# Adafruit-FONA-800-GSM-Breakout.net
KiCad netlist of a schematic drawn in EAGLE
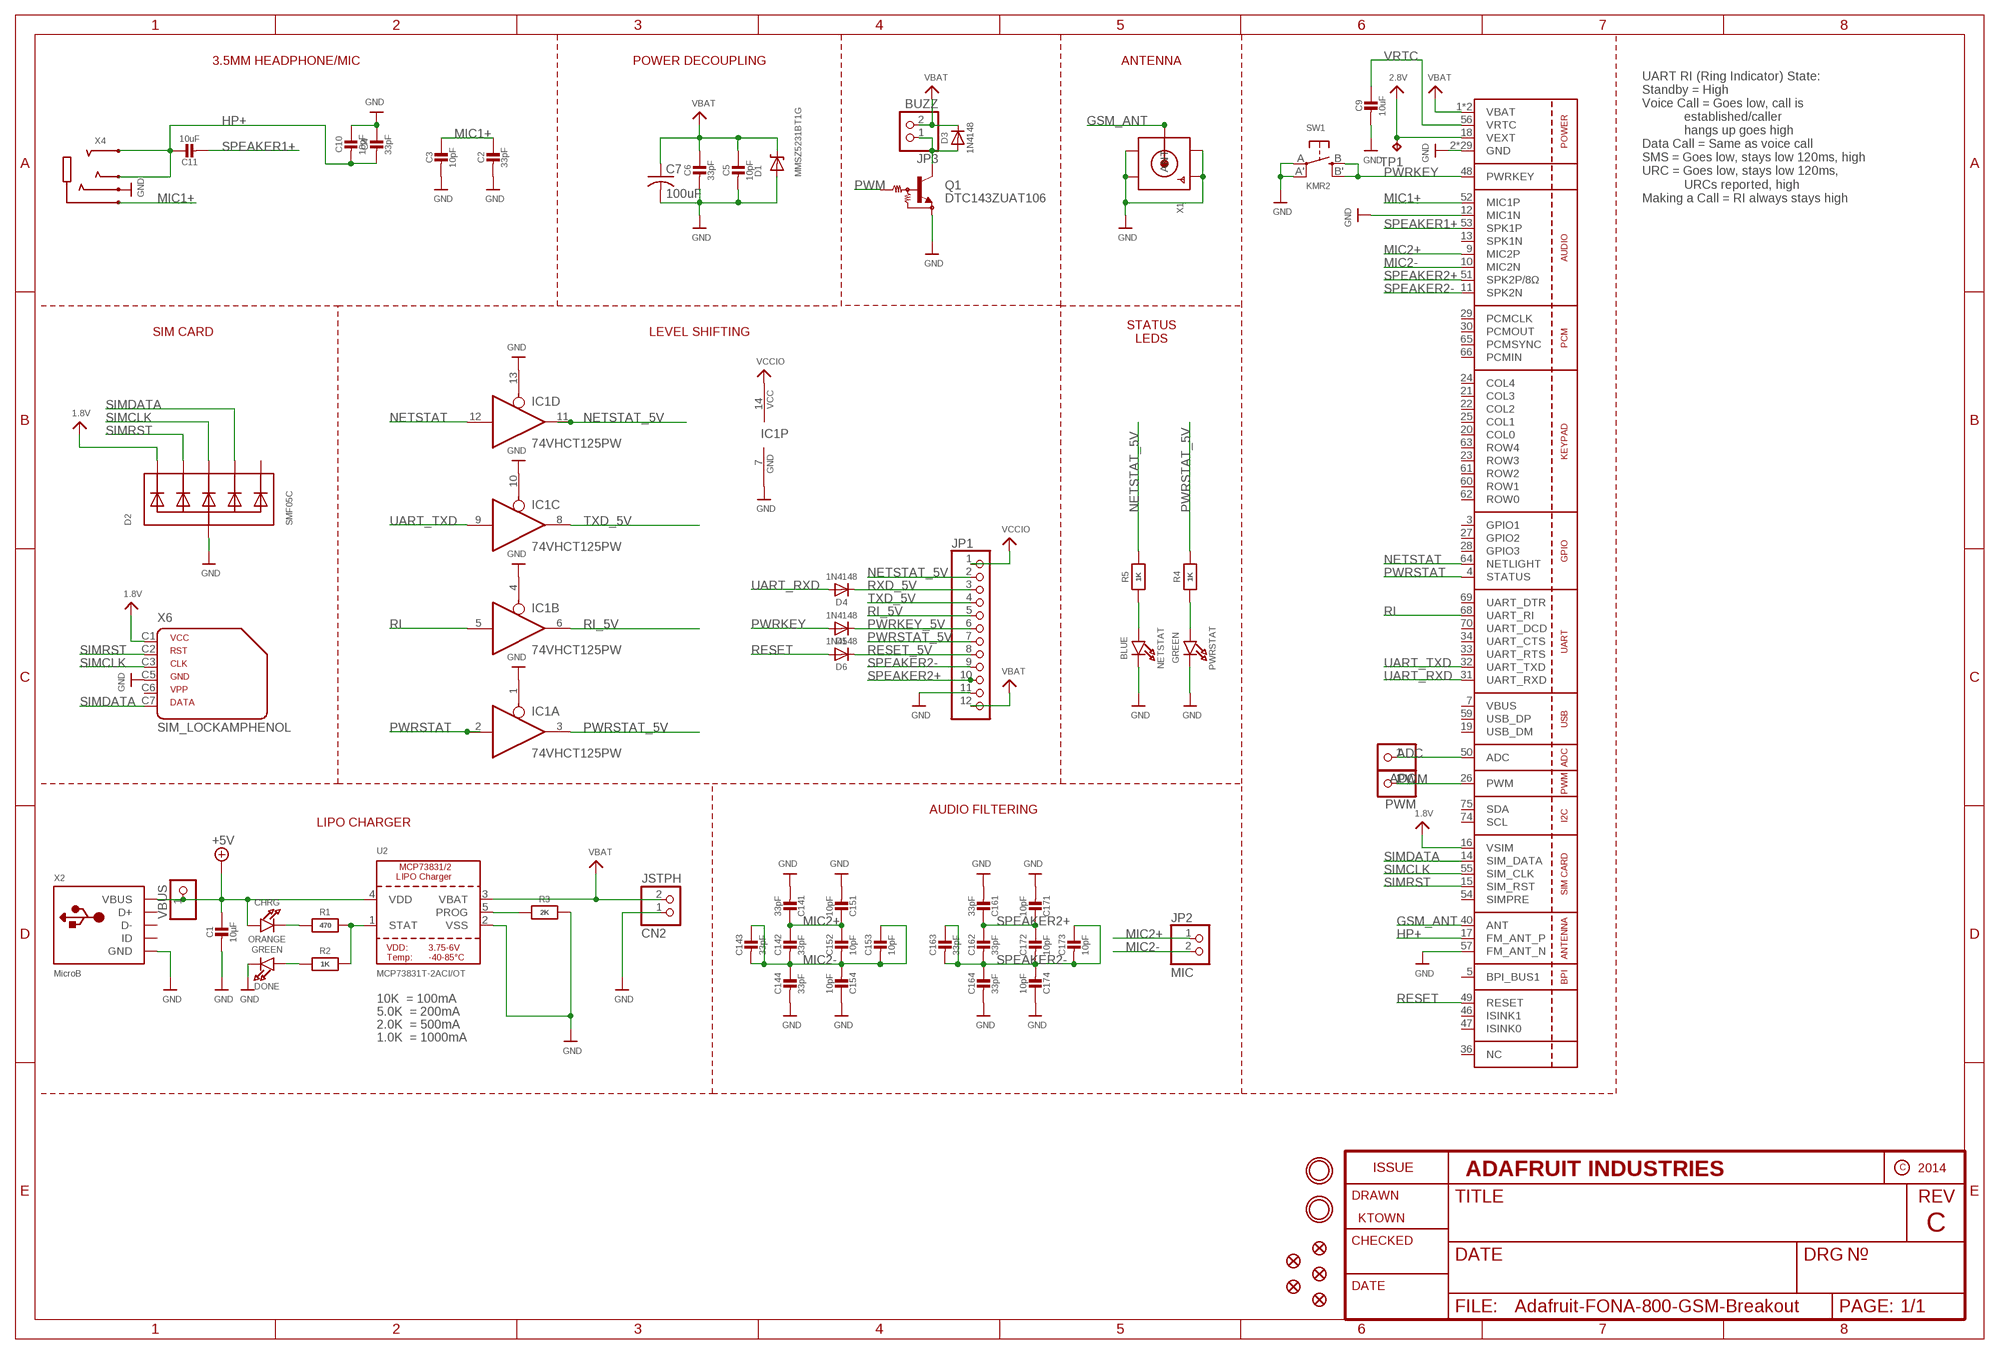
[diagram p0: schematic, sheet 1]

(export (version "E")
  (design (tool "Eeschema 10.0.6"))
  (components
    (comp (ref "ADC")
      (value "PINHD-1X1CB")
      (footprint "eagle-import:1X01-CLEANBIG")
      (libsource (lib "eagle-import") (part "PINHD-1X1CB"))
    )
    (comp (ref "C1")
      (value "10µF")
      (footprint "eagle-import:0805-NO")
      (libsource (lib "eagle-import") (part "CAP_CERAMIC0805-NOOUTLINE"))
    )
    (comp (ref "C2")
      (value "33pF")
      (footprint "eagle-import:0805-NO")
      (libsource (lib "eagle-import") (part "CAP_CERAMIC0805-NOOUTLINE"))
    )
    (comp (ref "C3")
      (value "10pF")
      (footprint "eagle-import:0805-NO")
      (libsource (lib "eagle-import") (part "CAP_CERAMIC0805-NOOUTLINE"))
    )
    (comp (ref "C4")
      (value "33pF")
      (footprint "eagle-import:0805-NO")
      (libsource (lib "eagle-import") (part "CAP_CERAMIC0805-NOOUTLINE"))
    )
    (comp (ref "C5")
      (value "10pF")
      (footprint "eagle-import:0805-NO")
      (libsource (lib "eagle-import") (part "CAP_CERAMIC0805-NOOUTLINE"))
    )
    (comp (ref "C6")
      (value "33pF")
      (footprint "eagle-import:0805-NO")
      (libsource (lib "eagle-import") (part "CAP_CERAMIC0805-NOOUTLINE"))
    )
    (comp (ref "C7")
      (value "100uF")
      (footprint "eagle-import:C1210")
      (libsource (lib "eagle-import") (part "C-USC1210"))
    )
    (comp (ref "C9")
      (value "10uF")
      (footprint "eagle-import:0805-NO")
      (libsource (lib "eagle-import") (part "CAP_CERAMIC0805-NOOUTLINE"))
    )
    (comp (ref "C10")
      (value "10pF")
      (footprint "eagle-import:0805-NO")
      (libsource (lib "eagle-import") (part "CAP_CERAMIC0805-NOOUTLINE"))
    )
    (comp (ref "C11")
      (value "10uF")
      (footprint "eagle-import:0805-NO")
      (libsource (lib "eagle-import") (part "CAP_CERAMIC0805-NOOUTLINE"))
    )
    (comp (ref "C14")
      (value "33pF")
      (footprint "eagle-import:RESPACK_4X0603")
      (libsource (lib "eagle-import") (part "CAP_4PACK1206"))
    )
    (comp (ref "C15")
      (value "10pF")
      (footprint "eagle-import:RESPACK_4X0603")
      (libsource (lib "eagle-import") (part "CAP_4PACK1206"))
    )
    (comp (ref "C16")
      (value "33pF")
      (footprint "eagle-import:RESPACK_4X0603")
      (libsource (lib "eagle-import") (part "CAP_4PACK1206"))
    )
    (comp (ref "C17")
      (value "10pF")
      (footprint "eagle-import:RESPACK_4X0603")
      (libsource (lib "eagle-import") (part "CAP_4PACK1206"))
    )
    (comp (ref "CHRG")
      (value "ORANGE")
      (footprint "eagle-import:CHIPLED_0805_NOOUTLINE")
      (libsource (lib "eagle-import") (part "LED0805_NOOUTLINE"))
    )
    (comp (ref "CN2")
      (value "JSTPH")
      (footprint "eagle-import:JSTPH2")
      (libsource (lib "eagle-import") (part "JST_2PIN"))
    )
    (comp (ref "D1")
      (value "MMSZ5231BT1G")
      (footprint "eagle-import:SOD-123")
      (libsource (lib "eagle-import") (part "DIODE-ZENERSOD123"))
    )
    (comp (ref "D2")
      (value "SMF05C")
      (footprint "eagle-import:SOT363")
      (libsource (lib "eagle-import") (part "TVSARRAY_5LANE"))
    )
    (comp (ref "D3")
      (value "1N4148")
      (footprint "eagle-import:SOD-323")
      (libsource (lib "eagle-import") (part "DIODESOD-323"))
    )
    (comp (ref "D4")
      (value "1N4148")
      (footprint "eagle-import:SOD-323")
      (libsource (lib "eagle-import") (part "DIODESOD-323"))
    )
    (comp (ref "D5")
      (value "1N4148")
      (footprint "eagle-import:SOD-323")
      (libsource (lib "eagle-import") (part "DIODESOD-323"))
    )
    (comp (ref "D6")
      (value "1N4148")
      (footprint "eagle-import:SOD-323")
      (libsource (lib "eagle-import") (part "DIODESOD-323"))
    )
    (comp (ref "DONE")
      (value "GREEN")
      (footprint "eagle-import:CHIPLED_0805_NOOUTLINE")
      (libsource (lib "eagle-import") (part "LED0805_NOOUTLINE"))
    )
    (comp (ref "FID1")
      (value "FIDUCIAL\"\"")
      (footprint "eagle-import:FIDUCIAL_1MM")
      (libsource (lib "eagle-import") (part "FIDUCIAL{dblquote}{dblquote}"))
    )
    (comp (ref "FID2")
      (value "FIDUCIAL\"\"")
      (footprint "eagle-import:FIDUCIAL_1MM")
      (libsource (lib "eagle-import") (part "FIDUCIAL{dblquote}{dblquote}"))
    )
    (comp (ref "FID3")
      (value "FIDUCIAL\"\"")
      (footprint "eagle-import:FIDUCIAL_1MM")
      (libsource (lib "eagle-import") (part "FIDUCIAL{dblquote}{dblquote}"))
    )
    (comp (ref "FID4")
      (value "FIDUCIAL\"\"")
      (footprint "eagle-import:FIDUCIAL_1MM")
      (libsource (lib "eagle-import") (part "FIDUCIAL{dblquote}{dblquote}"))
    )
    (comp (ref "FID5")
      (value "FIDUCIAL\"\"")
      (footprint "eagle-import:FIDUCIAL_1MM")
      (libsource (lib "eagle-import") (part "FIDUCIAL{dblquote}{dblquote}"))
    )
    (comp (ref "IC1")
      (value "74VHCT125PW")
      (footprint "eagle-import:TSSOP14")
      (libsource (lib "eagle-import") (part "74125PWABT"))
    )
    (comp (ref "JP1")
      (value "PINHD-1X12-CB")
      (footprint "eagle-import:1X12-CB")
      (libsource (lib "eagle-import") (part "PINHD-1X12-CB"))
    )
    (comp (ref "JP2")
      (value "MIC")
      (footprint "eagle-import:1X02_ROUND")
      (libsource (lib "eagle-import") (part "HEADER-1X2ROUND"))
    )
    (comp (ref "JP3")
      (value "BUZZ")
      (footprint "eagle-import:1X02_ROUND")
      (libsource (lib "eagle-import") (part "HEADER-1X2ROUND"))
    )
    (comp (ref "NETSTAT")
      (value "BLUE")
      (footprint "eagle-import:CHIPLED_0805_NOOUTLINE")
      (libsource (lib "eagle-import") (part "LED0805_NOOUTLINE"))
    )
    (comp (ref "PWM")
      (value "PINHD-1X1CB")
      (footprint "eagle-import:1X01-CLEANBIG")
      (libsource (lib "eagle-import") (part "PINHD-1X1CB"))
    )
    (comp (ref "PWRSTAT")
      (value "GREEN")
      (footprint "eagle-import:CHIPLED_0805_NOOUTLINE")
      (libsource (lib "eagle-import") (part "LED0805_NOOUTLINE"))
    )
    (comp (ref "Q1")
      (value "DTC143ZUAT106")
      (footprint "eagle-import:SC59-BEC")
      (libsource (lib "eagle-import") (part "-NPN_DRIVER-SC59-BECMUN2211T1"))
    )
    (comp (ref "R1")
      (value "470")
      (footprint "eagle-import:0805-NO")
      (libsource (lib "eagle-import") (part "RESISTOR0805_NOOUTLINE"))
    )
    (comp (ref "R2")
      (value "1K")
      (footprint "eagle-import:0805-NO")
      (libsource (lib "eagle-import") (part "RESISTOR0805_NOOUTLINE"))
    )
    (comp (ref "R3")
      (value "2K")
      (footprint "eagle-import:0805-NO")
      (libsource (lib "eagle-import") (part "RESISTOR0805_NOOUTLINE"))
    )
    (comp (ref "R4")
      (value "1K")
      (footprint "eagle-import:0805-NO")
      (libsource (lib "eagle-import") (part "RESISTOR0805_NOOUTLINE"))
    )
    (comp (ref "R5")
      (value "1K")
      (footprint "eagle-import:0805-NO")
      (libsource (lib "eagle-import") (part "RESISTOR0805_NOOUTLINE"))
    )
    (comp (ref "SW1")
      (value "KMR2")
      (footprint "eagle-import:BTN_KMR2_4.6X2.8")
      (libsource (lib "eagle-import") (part "SWITCH_TACT_SMT4.6X2.8"))
    )
    (comp (ref "TP1")
      (value "TPTP11R")
      (footprint "eagle-import:TP11R")
      (libsource (lib "eagle-import") (part "TPTP11R"))
    )
    (comp (ref "U$33")
      (value "MOUNTINGHOLE2.5")
      (footprint "eagle-import:MOUNTINGHOLE_2.5_PLATED")
      (libsource (lib "eagle-import") (part "MOUNTINGHOLE2.5"))
    )
    (comp (ref "U$34")
      (value "MOUNTINGHOLE2.5")
      (footprint "eagle-import:MOUNTINGHOLE_2.5_PLATED")
      (libsource (lib "eagle-import") (part "MOUNTINGHOLE2.5"))
    )
    (comp (ref "U1")
      (value "SIM800H/L")
      (footprint "eagle-import:SIM800L")
      (libsource (lib "eagle-import") (part "GSM_SIM800L"))
    )
    (comp (ref "U2")
      (value "MCP73831T-2ACI/OT")
      (footprint "eagle-import:SOT23-5")
      (libsource (lib "eagle-import") (part "MCP73831/2"))
    )
    (comp (ref "VBUS")
      (value "PINHD-1X1CB")
      (footprint "eagle-import:1X01-CLEANBIG")
      (libsource (lib "eagle-import") (part "PINHD-1X1CB"))
    )
    (comp (ref "X1")
      (value "SMACONNECTOR_EDGE_UFL")
      (footprint "eagle-import:SMA_EDGELAUNCH_UFL")
      (libsource (lib "eagle-import") (part "SMACONNECTOR_EDGE_UFL"))
    )
    (comp (ref "X2")
      (value "MicroB")
      (footprint "eagle-import:4UCONN_20329")
      (libsource (lib "eagle-import") (part "USBMICRO_20329"))
    )
    (comp (ref "X4")
      (value "AUDIO_3.5MMJACK_4POL")
      (footprint "eagle-import:4UCONN_18510")
      (libsource (lib "eagle-import") (part "AUDIO_3.5MMJACK_4POL"))
    )
    (comp (ref "X6")
      (value "SIM_LOCKAMPHENOL")
      (footprint "eagle-import:C707_10M006_512_2")
      (libsource (lib "eagle-import") (part "SIM_LOCKAMPHENOL"))
    )
  )
  (nets
    (net (code "1") (name "+5V") (class "Default")
      (node (ref "C1") (pin "1") (pinfunction "1_1") (pintype "passive"))
      (node (ref "CHRG") (pin "A") (pinfunction "A_A") (pintype "passive"))
      (node (ref "U2") (pin "4") (pinfunction "VDD_4") (pintype "power_in"))
      (node (ref "VBUS") (pin "1") (pinfunction "1_1") (pintype "passive"))
      (node (ref "X2") (pin "VBUS") (pinfunction "VBUS_VBUS") (pintype "power_in"))
    )
    (net (code "2") (name "/ADC") (class "Default")
      (node (ref "ADC") (pin "1") (pinfunction "1_1") (pintype "passive"))
      (node (ref "U1") (pin "50") (pinfunction "ADC_50") (pintype "input"))
    )
    (net (code "3") (name "/GSM_ANT") (class "Default")
      (node (ref "U1") (pin "40") (pinfunction "ANT_40") (pintype "bidirectional"))
      (node (ref "X1") (pin "P") (pinfunction "ANT_P") (pintype "bidirectional"))
    )
    (net (code "4") (name "/HP+") (class "Default")
      (node (ref "C10") (pin "2") (pinfunction "2_2") (pintype "passive"))
      (node (ref "C11") (pin "1") (pinfunction "1_1") (pintype "passive"))
      (node (ref "C4") (pin "2") (pinfunction "2_2") (pintype "passive"))
      (node (ref "U1") (pin "17") (pinfunction "FM_ANT_P_17") (pintype "bidirectional"))
      (node (ref "X4") (pin "2-TIP") (pinfunction "RING3_2-TIP") (pintype "passive"))
      (node (ref "X4") (pin "3-OUTER_SLEEVE") (pinfunction "RING2_3-OUTER_SLEEVE") (pintype "passive"))
    )
    (net (code "5") (name "/MIC1+") (class "Default")
      (node (ref "C2") (pin "1") (pinfunction "1_1") (pintype "passive"))
      (node (ref "C3") (pin "1") (pinfunction "1_1") (pintype "passive"))
      (node (ref "U1") (pin "52") (pinfunction "MIC1P_52") (pintype "input"))
      (node (ref "X4") (pin "1-GND") (pinfunction "TIP_1-GND") (pintype "passive"))
    )
    (net (code "6") (name "/MIC2+") (class "Default")
      (node (ref "C14") (pin "1") (pinfunction "1_1") (pintype "passive"))
      (node (ref "C14") (pin "2") (pinfunction "1_2") (pintype "passive"))
      (node (ref "C15") (pin "1") (pinfunction "1_1") (pintype "passive"))
      (node (ref "C15") (pin "2") (pinfunction "1_2") (pintype "passive"))
      (node (ref "JP2") (pin "1") (pinfunction "1_1") (pintype "passive"))
      (node (ref "U1") (pin "9") (pinfunction "MIC2P_9") (pintype "input"))
    )
    (net (code "7") (name "/MIC2-") (class "Default")
      (node (ref "C14") (pin "3") (pinfunction "1_3") (pintype "passive"))
      (node (ref "C14") (pin "4") (pinfunction "1_4") (pintype "passive"))
      (node (ref "C14") (pin "6") (pinfunction "2_6") (pintype "passive"))
      (node (ref "C14") (pin "7") (pinfunction "2_7") (pintype "passive"))
      (node (ref "C15") (pin "3") (pinfunction "1_3") (pintype "passive"))
      (node (ref "C15") (pin "5") (pinfunction "2_5") (pintype "passive"))
      (node (ref "C15") (pin "6") (pinfunction "2_6") (pintype "passive"))
      (node (ref "C15") (pin "7") (pinfunction "2_7") (pintype "passive"))
      (node (ref "JP2") (pin "2") (pinfunction "2_2") (pintype "passive"))
      (node (ref "U1") (pin "10") (pinfunction "MIC2N_10") (pintype "input"))
    )
    (net (code "8") (name "/NETSTAT") (class "Default")
      (node (ref "IC1") (pin "12") (pinfunction "I_12") (pintype "input"))
      (node (ref "U1") (pin "64") (pinfunction "NETLIGHT_64") (pintype "output"))
    )
    (net (code "9") (name "/NETSTAT_5V") (class "Default")
      (node (ref "IC1") (pin "11") (pinfunction "O_11") (pintype "tri_state"))
      (node (ref "JP1") (pin "2") (pinfunction "2_2") (pintype "passive"))
      (node (ref "R5") (pin "2") (pinfunction "2_2") (pintype "passive"))
    )
    (net (code "10") (name "/PWM") (class "Default")
      (node (ref "PWM") (pin "1") (pinfunction "1_1") (pintype "passive"))
      (node (ref "Q1") (pin "B") (pinfunction "B_B") (pintype "passive"))
      (node (ref "U1") (pin "26") (pinfunction "PWM_26") (pintype "output"))
    )
    (net (code "11") (name "/PWRKEY") (class "Default")
      (node (ref "D5") (pin "A") (pinfunction "A_A") (pintype "passive"))
      (node (ref "SW1") (pin "B") (pinfunction "S_B") (pintype "passive"))
      (node (ref "SW1") (pin "B'") (pinfunction "S1_B'") (pintype "passive"))
      (node (ref "U1") (pin "48") (pinfunction "PWRKEY_48") (pintype "input"))
    )
    (net (code "12") (name "/PWRKEY_5V") (class "Default")
      (node (ref "D5") (pin "C") (pinfunction "C_C") (pintype "passive"))
      (node (ref "JP1") (pin "6") (pinfunction "6_6") (pintype "passive"))
    )
    (net (code "13") (name "/PWRSTAT") (class "Default")
      (node (ref "IC1") (pin "2") (pinfunction "I_2") (pintype "input"))
      (node (ref "U1") (pin "4") (pinfunction "STATUS_4") (pintype "output"))
    )
    (net (code "14") (name "/PWRSTAT_5V") (class "Default")
      (node (ref "IC1") (pin "3") (pinfunction "O_3") (pintype "tri_state"))
      (node (ref "JP1") (pin "7") (pinfunction "7_7") (pintype "passive"))
      (node (ref "R4") (pin "2") (pinfunction "2_2") (pintype "passive"))
    )
    (net (code "15") (name "/RESET") (class "Default")
      (node (ref "D6") (pin "A") (pinfunction "A_A") (pintype "passive"))
      (node (ref "U1") (pin "49") (pinfunction "RESET_49") (pintype "input"))
    )
    (net (code "16") (name "/RESET_5V") (class "Default")
      (node (ref "D6") (pin "C") (pinfunction "C_C") (pintype "passive"))
      (node (ref "JP1") (pin "8") (pinfunction "8_8") (pintype "passive"))
    )
    (net (code "17") (name "/RI") (class "Default")
      (node (ref "IC1") (pin "5") (pinfunction "I_5") (pintype "input"))
      (node (ref "U1") (pin "68") (pinfunction "UART_RI_68") (pintype "output"))
    )
    (net (code "18") (name "/RI_5V") (class "Default")
      (node (ref "IC1") (pin "6") (pinfunction "O_6") (pintype "tri_state"))
      (node (ref "JP1") (pin "5") (pinfunction "5_5") (pintype "passive"))
    )
    (net (code "19") (name "/RXD_5V") (class "Default")
      (node (ref "D4") (pin "C") (pinfunction "C_C") (pintype "passive"))
      (node (ref "JP1") (pin "3") (pinfunction "3_3") (pintype "passive"))
    )
    (net (code "20") (name "/SIMCLK") (class "Default")
      (node (ref "D2") (pin "4") (pinfunction "C3_4") (pintype "passive"))
      (node (ref "U1") (pin "55") (pinfunction "SIM_CLK_55") (pintype "output"))
      (node (ref "X6") (pin "C3") (pinfunction "3_C3") (pintype "passive"))
    )
    (net (code "21") (name "/SIMDATA") (class "Default")
      (node (ref "D2") (pin "5") (pinfunction "C4_5") (pintype "passive"))
      (node (ref "U1") (pin "14") (pinfunction "SIM_DATA_14") (pintype "bidirectional"))
      (node (ref "X6") (pin "C7") (pinfunction "6_C7") (pintype "passive"))
    )
    (net (code "22") (name "/SIMRST") (class "Default")
      (node (ref "D2") (pin "3") (pinfunction "C2_3") (pintype "passive"))
      (node (ref "U1") (pin "15") (pinfunction "SIM_RST_15") (pintype "output"))
      (node (ref "X6") (pin "C2") (pinfunction "2_C2") (pintype "passive"))
    )
    (net (code "23") (name "/SPEAKER1+") (class "Default")
      (node (ref "C11") (pin "2") (pinfunction "2_2") (pintype "passive"))
      (node (ref "U1") (pin "53") (pinfunction "SPK1P_53") (pintype "output"))
    )
    (net (code "24") (name "/SPEAKER2+") (class "Default")
      (node (ref "C16") (pin "1") (pinfunction "1_1") (pintype "passive"))
      (node (ref "C16") (pin "2") (pinfunction "1_2") (pintype "passive"))
      (node (ref "C17") (pin "1") (pinfunction "1_1") (pintype "passive"))
      (node (ref "C17") (pin "2") (pinfunction "1_2") (pintype "passive"))
      (node (ref "JP1") (pin "10") (pinfunction "10_10") (pintype "passive"))
      (node (ref "U1") (pin "51") (pinfunction "SPK2P/8Ω_51") (pintype "output"))
    )
    (net (code "25") (name "/SPEAKER2-") (class "Default")
      (node (ref "C16") (pin "3") (pinfunction "1_3") (pintype "passive"))
      (node (ref "C16") (pin "4") (pinfunction "1_4") (pintype "passive"))
      (node (ref "C16") (pin "6") (pinfunction "2_6") (pintype "passive"))
      (node (ref "C16") (pin "7") (pinfunction "2_7") (pintype "passive"))
      (node (ref "C17") (pin "3") (pinfunction "1_3") (pintype "passive"))
      (node (ref "C17") (pin "5") (pinfunction "2_5") (pintype "passive"))
      (node (ref "C17") (pin "6") (pinfunction "2_6") (pintype "passive"))
      (node (ref "C17") (pin "7") (pinfunction "2_7") (pintype "passive"))
      (node (ref "JP1") (pin "9") (pinfunction "9_9") (pintype "passive"))
      (node (ref "U1") (pin "11") (pinfunction "SPK2N_11") (pintype "output"))
    )
    (net (code "26") (name "/TXD_5V") (class "Default")
      (node (ref "IC1") (pin "8") (pinfunction "O_8") (pintype "tri_state"))
      (node (ref "JP1") (pin "4") (pinfunction "4_4") (pintype "passive"))
    )
    (net (code "27") (name "/UART_RXD") (class "Default")
      (node (ref "D4") (pin "A") (pinfunction "A_A") (pintype "passive"))
      (node (ref "U1") (pin "31") (pinfunction "UART_RXD_31") (pintype "input"))
    )
    (net (code "28") (name "/UART_TXD") (class "Default")
      (node (ref "IC1") (pin "9") (pinfunction "I_9") (pintype "input"))
      (node (ref "U1") (pin "32") (pinfunction "UART_TXD_32") (pintype "output"))
    )
    (net (code "29") (name "/VBUS") (class "Default")
      (node (ref "U1") (pin "7") (pinfunction "VBUS_7") (pintype "power_in"))
    )
    (net (code "30") (name "/VRTC") (class "Default")
      (node (ref "C9") (pin "1") (pinfunction "1_1") (pintype "passive"))
      (node (ref "U1") (pin "56") (pinfunction "VRTC_56") (pintype "power_in"))
    )
    (net (code "31") (name "1.8V") (class "Default")
      (node (ref "D2") (pin "1") (pinfunction "C1_1") (pintype "passive"))
      (node (ref "U1") (pin "16") (pinfunction "VSIM_16") (pintype "power_in"))
      (node (ref "X6") (pin "C1") (pinfunction "1_C1") (pintype "passive"))
    )
    (net (code "32") (name "2.8V") (class "Default")
      (node (ref "TP1") (pin "TP") (pinfunction "TP_TP") (pintype "input"))
      (node (ref "U1") (pin "18") (pinfunction "VEXT_18") (pintype "power_in"))
    )
    (net (code "33") (name "GND") (class "Default")
      (node (ref "C1") (pin "2") (pinfunction "2_2") (pintype "passive"))
      (node (ref "C10") (pin "1") (pinfunction "1_1") (pintype "passive"))
      (node (ref "C14") (pin "5") (pinfunction "2_5") (pintype "passive"))
      (node (ref "C14") (pin "8") (pinfunction "2_8") (pintype "passive"))
      (node (ref "C15") (pin "4") (pinfunction "1_4") (pintype "passive"))
      (node (ref "C15") (pin "8") (pinfunction "2_8") (pintype "passive"))
      (node (ref "C16") (pin "5") (pinfunction "2_5") (pintype "passive"))
      (node (ref "C16") (pin "8") (pinfunction "2_8") (pintype "passive"))
      (node (ref "C17") (pin "4") (pinfunction "1_4") (pintype "passive"))
      (node (ref "C17") (pin "8") (pinfunction "2_8") (pintype "passive"))
      (node (ref "C2") (pin "2") (pinfunction "2_2") (pintype "passive"))
      (node (ref "C3") (pin "2") (pinfunction "2_2") (pintype "passive"))
      (node (ref "C4") (pin "1") (pinfunction "1_1") (pintype "passive"))
      (node (ref "C5") (pin "2") (pinfunction "2_2") (pintype "passive"))
      (node (ref "C6") (pin "2") (pinfunction "2_2") (pintype "passive"))
      (node (ref "C7") (pin "2") (pinfunction "2_2") (pintype "passive"))
      (node (ref "C9") (pin "2") (pinfunction "2_2") (pintype "passive"))
      (node (ref "CN2") (pin "1") (pinfunction "1_1") (pintype "passive"))
      (node (ref "D1") (pin "A") (pinfunction "A_A") (pintype "passive"))
      (node (ref "D2") (pin "2") (pinfunction "A_2") (pintype "passive"))
      (node (ref "DONE") (pin "C") (pinfunction "C_C") (pintype "passive"))
      (node (ref "IC1") (pin "1") (pinfunction "OE_1") (pintype "input"))
      (node (ref "IC1") (pin "10") (pinfunction "OE_10") (pintype "input"))
      (node (ref "IC1") (pin "13") (pinfunction "OE_13") (pintype "input"))
      (node (ref "IC1") (pin "4") (pinfunction "OE_4") (pintype "input"))
      (node (ref "IC1") (pin "7") (pinfunction "GND_7") (pintype "power_in"))
      (node (ref "JP1") (pin "11") (pinfunction "11_11") (pintype "passive"))
      (node (ref "NETSTAT") (pin "C") (pinfunction "C_C") (pintype "passive"))
      (node (ref "PWRSTAT") (pin "C") (pinfunction "C_C") (pintype "passive"))
      (node (ref "Q1") (pin "E") (pinfunction "E_E") (pintype "passive"))
      (node (ref "R3") (pin "2") (pinfunction "2_2") (pintype "passive"))
      (node (ref "SW1") (pin "A") (pinfunction "P_A") (pintype "passive"))
      (node (ref "SW1") (pin "A'") (pinfunction "P1_A'") (pintype "passive"))
      (node (ref "U1") (pin "12") (pinfunction "MIC1N_12") (pintype "input"))
      (node (ref "U1") (pin "2") (pinfunction "GND_2") (pintype "power_in"))
      (node (ref "U1") (pin "35") (pinfunction "GND_35") (pintype "power_in"))
      (node (ref "U1") (pin "37") (pinfunction "GND_37") (pintype "power_in"))
      (node (ref "U1") (pin "38") (pinfunction "GND_38") (pintype "power_in"))
      (node (ref "U1") (pin "39") (pinfunction "GND_39") (pintype "power_in"))
      (node (ref "U1") (pin "41") (pinfunction "GND_41") (pintype "power_in"))
      (node (ref "U1") (pin "43") (pinfunction "GND_43") (pintype "power_in"))
      (node (ref "U1") (pin "44") (pinfunction "GND_44") (pintype "power_in"))
      (node (ref "U1") (pin "45") (pinfunction "GND_45") (pintype "power_in"))
      (node (ref "U1") (pin "57") (pinfunction "FM_ANT_N_57") (pintype "bidirectional"))
      (node (ref "U1") (pin "58") (pinfunction "GND_58") (pintype "power_in"))
      (node (ref "U1") (pin "6") (pinfunction "GND_6") (pintype "power_in"))
      (node (ref "U1") (pin "67") (pinfunction "GND_67") (pintype "power_in"))
      (node (ref "U1") (pin "71") (pinfunction "GND_71") (pintype "power_in"))
      (node (ref "U1") (pin "72") (pinfunction "GND_72") (pintype "power_in"))
      (node (ref "U1") (pin "73") (pinfunction "GND_73") (pintype "power_in"))
      (node (ref "U1") (pin "76") (pinfunction "GND_76") (pintype "power_in"))
      (node (ref "U1") (pin "77") (pinfunction "GND_77") (pintype "power_in"))
      (node (ref "U1") (pin "78") (pinfunction "GND_78") (pintype "power_in"))
      (node (ref "U1") (pin "79") (pinfunction "GND_79") (pintype "power_in"))
      (node (ref "U1") (pin "8") (pinfunction "GND_8") (pintype "power_in"))
      (node (ref "U1") (pin "80") (pinfunction "GND_80") (pintype "power_in"))
      (node (ref "U1") (pin "81") (pinfunction "GND_81") (pintype "power_in"))
      (node (ref "U1") (pin "82") (pinfunction "GND_82") (pintype "power_in"))
      (node (ref "U1") (pin "83") (pinfunction "GND_83") (pintype "power_in"))
      (node (ref "U1") (pin "84") (pinfunction "GND_84") (pintype "power_in"))
      (node (ref "U1") (pin "85") (pinfunction "GND_85") (pintype "power_in"))
      (node (ref "U1") (pin "86") (pinfunction "GND_86") (pintype "power_in"))
      (node (ref "U1") (pin "87") (pinfunction "GND_87") (pintype "power_in"))
      (node (ref "U1") (pin "88") (pinfunction "GND_88") (pintype "power_in"))
      (node (ref "U2") (pin "2") (pinfunction "VSS_2") (pintype "power_in"))
      (node (ref "X1") (pin "GND@1") (pinfunction "GND1_GND@1") (pintype "power_in"))
      (node (ref "X1") (pin "GND@2") (pinfunction "GND2_GND@2") (pintype "power_in"))
      (node (ref "X1") (pin "GND@3") (pinfunction "GND3_GND@3") (pintype "power_in"))
      (node (ref "X1") (pin "GND@4") (pinfunction "GND4_GND@4") (pintype "power_in"))
      (node (ref "X2") (pin "BASE@1") (pinfunction "GND_BASE@1") (pintype "power_in"))
      (node (ref "X2") (pin "BASE@2") (pinfunction "GND_BASE@2") (pintype "power_in"))
      (node (ref "X2") (pin "GND") (pinfunction "GND_GND") (pintype "power_in"))
      (node (ref "X2") (pin "SPRT@1") (pinfunction "GND_SPRT@1") (pintype "power_in"))
      (node (ref "X2") (pin "SPRT@2") (pinfunction "GND_SPRT@2") (pintype "power_in"))
      (node (ref "X2") (pin "SPRT@3") (pinfunction "GND_SPRT@3") (pintype "power_in"))
      (node (ref "X2") (pin "SPRT@4") (pinfunction "GND_SPRT@4") (pintype "power_in"))
      (node (ref "X4") (pin "4-INNER_SLEEVE") (pinfunction "RING1_4-INNER_SLEEVE") (pintype "passive"))
      (node (ref "X6") (pin "C5") (pinfunction "4_C5") (pintype "passive"))
    )
    (net (code "34") (name "Net-(CHRG-PadC)") (class "Default")
      (node (ref "CHRG") (pin "C") (pinfunction "C_C") (pintype "passive"))
      (node (ref "R1") (pin "1") (pinfunction "1_1") (pintype "passive"))
    )
    (net (code "35") (name "Net-(D3-PadA)") (class "Default")
      (node (ref "D3") (pin "A") (pinfunction "A_A") (pintype "passive"))
      (node (ref "JP3") (pin "1") (pinfunction "1_1") (pintype "passive"))
      (node (ref "Q1") (pin "C") (pinfunction "C_C") (pintype "passive"))
    )
    (net (code "36") (name "Net-(DONE-PadA)") (class "Default")
      (node (ref "DONE") (pin "A") (pinfunction "A_A") (pintype "passive"))
      (node (ref "R2") (pin "1") (pinfunction "1_1") (pintype "passive"))
    )
    (net (code "37") (name "Net-(NETSTAT-PadA)") (class "Default")
      (node (ref "NETSTAT") (pin "A") (pinfunction "A_A") (pintype "passive"))
      (node (ref "R5") (pin "1") (pinfunction "1_1") (pintype "passive"))
    )
    (net (code "38") (name "Net-(PWRSTAT-PadA)") (class "Default")
      (node (ref "PWRSTAT") (pin "A") (pinfunction "A_A") (pintype "passive"))
      (node (ref "R4") (pin "1") (pinfunction "1_1") (pintype "passive"))
    )
    (net (code "39") (name "Net-(U2-PROG)") (class "Default")
      (node (ref "R3") (pin "1") (pinfunction "1_1") (pintype "passive"))
      (node (ref "U2") (pin "5") (pinfunction "PROG_5") (pintype "input"))
    )
    (net (code "40") (name "Net-(U2-STAT)") (class "Default")
      (node (ref "R1") (pin "2") (pinfunction "2_2") (pintype "passive"))
      (node (ref "R2") (pin "2") (pinfunction "2_2") (pintype "passive"))
      (node (ref "U2") (pin "1") (pinfunction "STAT_1") (pintype "output"))
    )
    (net (code "41") (name "VBAT") (class "Default")
      (node (ref "C5") (pin "1") (pinfunction "1_1") (pintype "passive"))
      (node (ref "C6") (pin "1") (pinfunction "1_1") (pintype "passive"))
      (node (ref "C7") (pin "1") (pinfunction "1_1") (pintype "passive"))
      (node (ref "CN2") (pin "2") (pinfunction "2_2") (pintype "passive"))
      (node (ref "D1") (pin "C") (pinfunction "C_C") (pintype "passive"))
      (node (ref "D3") (pin "C") (pinfunction "C_C") (pintype "passive"))
      (node (ref "JP1") (pin "12") (pinfunction "12_12") (pintype "passive"))
      (node (ref "JP3") (pin "2") (pinfunction "2_2") (pintype "passive"))
      (node (ref "U1") (pin "1") (pinfunction "VBAT_1") (pintype "power_in"))
      (node (ref "U1") (pin "42") (pinfunction "VBAT_42") (pintype "power_in"))
      (node (ref "U2") (pin "3") (pinfunction "VBAT_3") (pintype "power_in"))
    )
    (net (code "42") (name "VCCIO") (class "Default")
      (node (ref "IC1") (pin "14") (pinfunction "VCC_14") (pintype "power_in"))
      (node (ref "JP1") (pin "1") (pinfunction "1_1") (pintype "passive"))
    )
    (net (code "43") (name "unconnected-(D2-C5-Pad6)") (class "Default")
      (node (ref "D2") (pin "6") (pinfunction "C5_6") (pintype "passive"))
    )
    (net (code "44") (name "unconnected-(U1-BPI_BUS1-Pad5)") (class "Default")
      (node (ref "U1") (pin "5") (pinfunction "BPI_BUS1_5") (pintype "output"))
    )
    (net (code "45") (name "unconnected-(U1-COL0-Pad20)") (class "Default")
      (node (ref "U1") (pin "20") (pinfunction "COL0_20") (pintype "bidirectional"))
    )
    (net (code "46") (name "unconnected-(U1-COL1-Pad25)") (class "Default")
      (node (ref "U1") (pin "25") (pinfunction "COL1_25") (pintype "bidirectional"))
    )
    (net (code "47") (name "unconnected-(U1-COL2-Pad22)") (class "Default")
      (node (ref "U1") (pin "22") (pinfunction "COL2_22") (pintype "bidirectional"))
    )
    (net (code "48") (name "unconnected-(U1-COL3-Pad21)") (class "Default")
      (node (ref "U1") (pin "21") (pinfunction "COL3_21") (pintype "bidirectional"))
    )
    (net (code "49") (name "unconnected-(U1-COL4-Pad24)") (class "Default")
      (node (ref "U1") (pin "24") (pinfunction "COL4_24") (pintype "bidirectional"))
    )
    (net (code "50") (name "unconnected-(U1-GPIO1-Pad3)") (class "Default")
      (node (ref "U1") (pin "3") (pinfunction "GPIO1_3") (pintype "bidirectional"))
    )
    (net (code "51") (name "unconnected-(U1-GPIO2-Pad27)") (class "Default")
      (node (ref "U1") (pin "27") (pinfunction "GPIO2_27") (pintype "bidirectional"))
    )
    (net (code "52") (name "unconnected-(U1-GPIO3-Pad28)") (class "Default")
      (node (ref "U1") (pin "28") (pinfunction "GPIO3_28") (pintype "bidirectional"))
    )
    (net (code "53") (name "unconnected-(U1-ISINK0-Pad47)") (class "Default")
      (node (ref "U1") (pin "47") (pinfunction "ISINK0_47") (pintype "input"))
    )
    (net (code "54") (name "unconnected-(U1-ISINK1-Pad46)") (class "Default")
      (node (ref "U1") (pin "46") (pinfunction "ISINK1_46") (pintype "input"))
    )
    (net (code "55") (name "unconnected-(U1-NC-Pad36)") (class "Default")
      (node (ref "U1") (pin "36") (pinfunction "NC_36") (pintype "no_connect"))
    )
    (net (code "56") (name "unconnected-(U1-PCMCLK-Pad29)") (class "Default")
      (node (ref "U1") (pin "29") (pinfunction "PCMCLK_29") (pintype "output"))
    )
    (net (code "57") (name "unconnected-(U1-PCMIN-Pad66)") (class "Default")
      (node (ref "U1") (pin "66") (pinfunction "PCMIN_66") (pintype "input"))
    )
    (net (code "58") (name "unconnected-(U1-PCMOUT-Pad30)") (class "Default")
      (node (ref "U1") (pin "30") (pinfunction "PCMOUT_30") (pintype "output"))
    )
    (net (code "59") (name "unconnected-(U1-PCMSYNC-Pad65)") (class "Default")
      (node (ref "U1") (pin "65") (pinfunction "PCMSYNC_65") (pintype "output"))
    )
    (net (code "60") (name "unconnected-(U1-ROW0-Pad62)") (class "Default")
      (node (ref "U1") (pin "62") (pinfunction "ROW0_62") (pintype "bidirectional"))
    )
    (net (code "61") (name "unconnected-(U1-ROW1-Pad60)") (class "Default")
      (node (ref "U1") (pin "60") (pinfunction "ROW1_60") (pintype "bidirectional"))
    )
    (net (code "62") (name "unconnected-(U1-ROW2-Pad61)") (class "Default")
      (node (ref "U1") (pin "61") (pinfunction "ROW2_61") (pintype "bidirectional"))
    )
    (net (code "63") (name "unconnected-(U1-ROW3-Pad23)") (class "Default")
      (node (ref "U1") (pin "23") (pinfunction "ROW3_23") (pintype "bidirectional"))
    )
    (net (code "64") (name "unconnected-(U1-ROW4-Pad63)") (class "Default")
      (node (ref "U1") (pin "63") (pinfunction "ROW4_63") (pintype "bidirectional"))
    )
    (net (code "65") (name "unconnected-(U1-SCL-Pad74)") (class "Default")
      (node (ref "U1") (pin "74") (pinfunction "SCL_74") (pintype "bidirectional"))
    )
    (net (code "66") (name "unconnected-(U1-SDA-Pad75)") (class "Default")
      (node (ref "U1") (pin "75") (pinfunction "SDA_75") (pintype "bidirectional"))
    )
    (net (code "67") (name "unconnected-(U1-SIMPRE-Pad54)") (class "Default")
      (node (ref "U1") (pin "54") (pinfunction "SIMPRE_54") (pintype "input"))
    )
    (net (code "68") (name "unconnected-(U1-SPK1N-Pad13)") (class "Default")
      (node (ref "U1") (pin "13") (pinfunction "SPK1N_13") (pintype "output"))
    )
    (net (code "69") (name "unconnected-(U1-UART_CTS-Pad34)") (class "Default")
      (node (ref "U1") (pin "34") (pinfunction "UART_CTS_34") (pintype "output"))
    )
    (net (code "70") (name "unconnected-(U1-UART_DCD-Pad70)") (class "Default")
      (node (ref "U1") (pin "70") (pinfunction "UART_DCD_70") (pintype "input"))
    )
    (net (code "71") (name "unconnected-(U1-UART_DTR-Pad69)") (class "Default")
      (node (ref "U1") (pin "69") (pinfunction "UART_DTR_69") (pintype "input"))
    )
    (net (code "72") (name "unconnected-(U1-UART_RTS-Pad33)") (class "Default")
      (node (ref "U1") (pin "33") (pinfunction "UART_RTS_33") (pintype "input"))
    )
    (net (code "73") (name "unconnected-(U1-USB_DM-Pad19)") (class "Default")
      (node (ref "U1") (pin "19") (pinfunction "USB_DM_19") (pintype "bidirectional"))
    )
    (net (code "74") (name "unconnected-(U1-USB_DP-Pad59)") (class "Default")
      (node (ref "U1") (pin "59") (pinfunction "USB_DP_59") (pintype "bidirectional"))
    )
    (net (code "75") (name "unconnected-(X2-PadD+)") (class "Default")
      (node (ref "X2") (pin "D+") (pinfunction "D+_D+") (pintype "bidirectional"))
    )
    (net (code "76") (name "unconnected-(X2-PadD-)") (class "Default")
      (node (ref "X2") (pin "D-") (pinfunction "D-_D-") (pintype "bidirectional"))
    )
    (net (code "77") (name "unconnected-(X2-PadID)") (class "Default")
      (node (ref "X2") (pin "ID") (pinfunction "ID_ID") (pintype "bidirectional"))
    )
    (net (code "78") (name "unconnected-(X6-5-PadC6)") (class "Default")
      (node (ref "X6") (pin "C6") (pinfunction "5_C6") (pintype "passive"))
    )
  )
)
